# 05_SAMA5D27SOM.net
KiCad netlist of a schematic drawn in Altium Designer
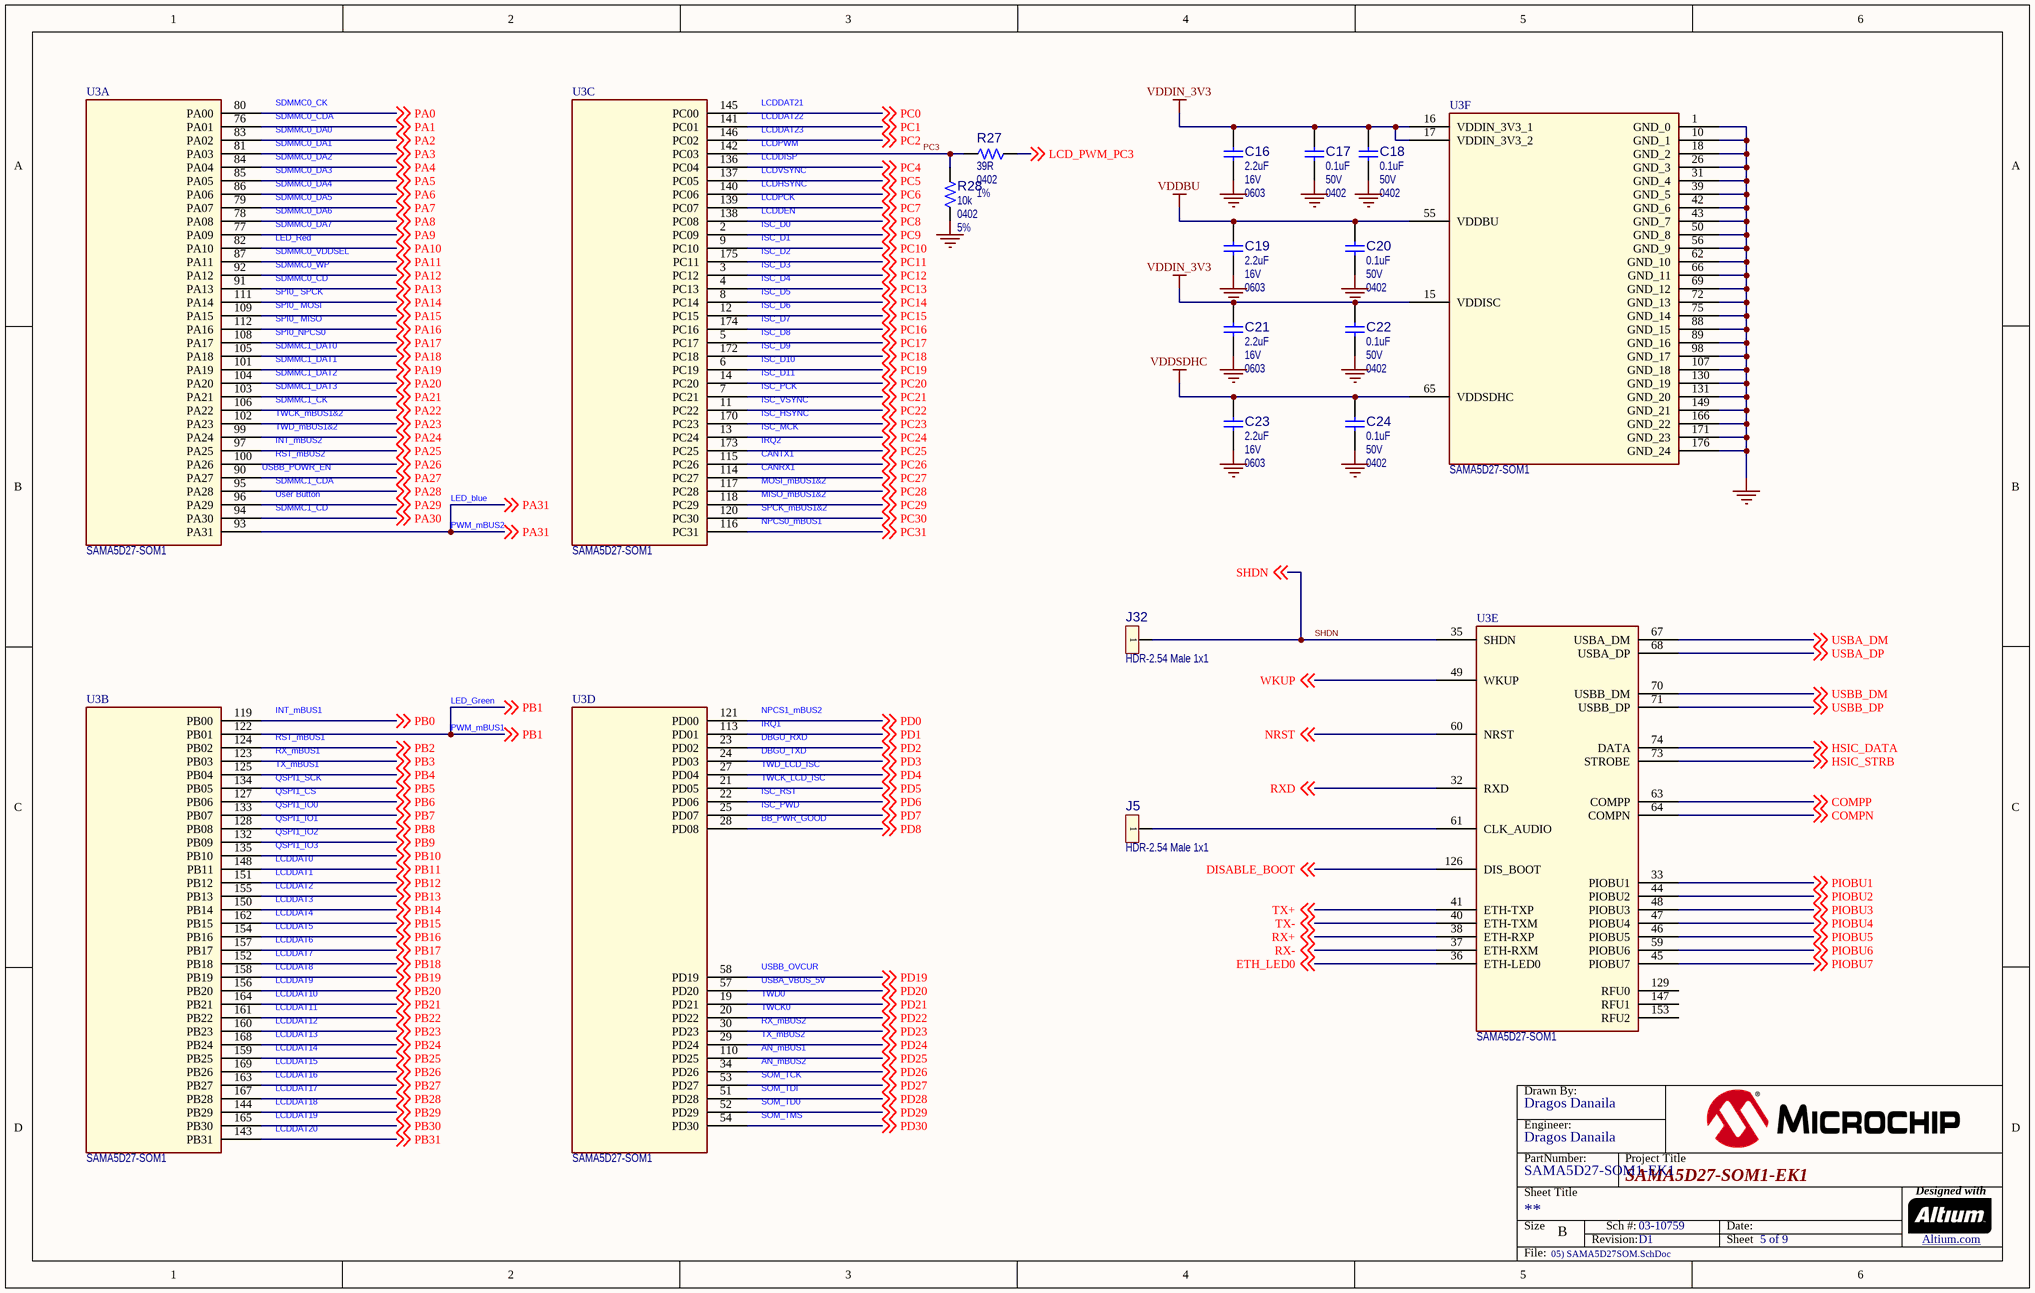
[diagram p0: 05) SAMA5D27SOM.SchDoc]

(export (version "E")
  (design (tool "Eeschema 10.0.6"))
  (components
    (comp (ref "C16")
      (value "2.2uF")
      (footprint "CAP_C_0603")
      (description "Capacitor")
      (fields
        (field (name "VOLTAGE") "16V")
        (field (name "PACKAGE") "0603")
        (field (name "TOLERANCE") "10%")
        (field (name "Comment") "Capacitor NP")
      )
      (libsource (lib "MCHP-CDB") (part "Capacitor NP"))
    )
    (comp (ref "C17")
      (value "0.1uF")
      (footprint "CAP_C_0402")
      (description "Capacitor")
      (fields
        (field (name "VOLTAGE") "50V")
        (field (name "PACKAGE") "0402")
        (field (name "TOLERANCE") "10%")
        (field (name "Comment") "Capacitor NP")
        (field (name "OWNER") "Jamus Griego")
      )
      (libsource (lib "MCHP-CDB") (part "Capacitor NP"))
    )
    (comp (ref "C18")
      (value "0.1uF")
      (footprint "CAP_C_0402")
      (description "Capacitor")
      (fields
        (field (name "VOLTAGE") "50V")
        (field (name "PACKAGE") "0402")
        (field (name "TOLERANCE") "10%")
        (field (name "Comment") "Capacitor NP")
        (field (name "OWNER") "Jamus Griego")
      )
      (libsource (lib "MCHP-CDB") (part "Capacitor NP"))
    )
    (comp (ref "C19")
      (value "2.2uF")
      (footprint "CAP_C_0603")
      (description "Capacitor")
      (fields
        (field (name "VOLTAGE") "16V")
        (field (name "PACKAGE") "0603")
        (field (name "TOLERANCE") "10%")
        (field (name "Comment") "Capacitor NP")
      )
      (libsource (lib "MCHP-CDB") (part "Capacitor NP"))
    )
    (comp (ref "C20")
      (value "0.1uF")
      (footprint "CAP_C_0402")
      (description "Capacitor")
      (fields
        (field (name "VOLTAGE") "50V")
        (field (name "PACKAGE") "0402")
        (field (name "TOLERANCE") "10%")
        (field (name "Comment") "Capacitor NP")
        (field (name "OWNER") "Jamus Griego")
      )
      (libsource (lib "MCHP-CDB") (part "Capacitor NP"))
    )
    (comp (ref "C21")
      (value "2.2uF")
      (footprint "CAP_C_0603")
      (description "Capacitor")
      (fields
        (field (name "VOLTAGE") "16V")
        (field (name "PACKAGE") "0603")
        (field (name "TOLERANCE") "10%")
        (field (name "Comment") "Capacitor NP")
      )
      (libsource (lib "MCHP-CDB") (part "Capacitor NP"))
    )
    (comp (ref "C22")
      (value "0.1uF")
      (footprint "CAP_C_0402")
      (description "Capacitor")
      (fields
        (field (name "VOLTAGE") "50V")
        (field (name "PACKAGE") "0402")
        (field (name "TOLERANCE") "10%")
        (field (name "Comment") "Capacitor NP")
        (field (name "OWNER") "Jamus Griego")
      )
      (libsource (lib "MCHP-CDB") (part "Capacitor NP"))
    )
    (comp (ref "C23")
      (value "2.2uF")
      (footprint "CAP_C_0603")
      (description "Capacitor")
      (fields
        (field (name "VOLTAGE") "16V")
        (field (name "PACKAGE") "0603")
        (field (name "TOLERANCE") "10%")
        (field (name "Comment") "Capacitor NP")
      )
      (libsource (lib "MCHP-CDB") (part "Capacitor NP"))
    )
    (comp (ref "C24")
      (value "0.1uF")
      (footprint "CAP_C_0402")
      (description "Capacitor")
      (fields
        (field (name "VOLTAGE") "50V")
        (field (name "PACKAGE") "0402")
        (field (name "TOLERANCE") "10%")
        (field (name "Comment") "Capacitor NP")
        (field (name "OWNER") "Jamus Griego")
      )
      (libsource (lib "MCHP-CDB") (part "Capacitor NP"))
    )
    (comp (ref "J5")
      (value "HDR-2.54 Male 1x1")
      (footprint "HDR_M_2.54_1x1")
      (description "CON HDR-2.54 Male 1x1 Gold 5.97MH TH VERT")
      (fields (field (name "Comment") "Header 1x1"))
      (libsource (lib "MCHP-CDB") (part "Header 1x1"))
    )
    (comp (ref "J32")
      (value "HDR-2.54 Male 1x1")
      (footprint "HDR_M_2.54_1x1")
      (description "CON HDR-2.54 Male 1x1 Gold 5.97MH TH VERT")
      (fields (field (name "Comment") "Header 1x1"))
      (libsource (lib "MCHP-CDB") (part "Header 1x1"))
    )
    (comp (ref "R27")
      (value "39R")
      (footprint "RES_C_0402")
      (description "Resistor")
      (fields
        (field (name "PACKAGE") "0402")
        (field (name "TOLERANCE") "1%")
        (field (name "POWER") "1/16W")
        (field (name "OWNER") "Sompoch Loboonlert")
      )
      (libsource (lib "MCHP-CDB") (part "Resistor"))
    )
    (comp (ref "R28")
      (value "10k")
      (footprint "RES_C_0402")
      (description "Resistor")
      (fields
        (field (name "PACKAGE") "0402")
        (field (name "TOLERANCE") "5%")
        (field (name "VOLTAGE") "50V")
        (field (name "POWER") "1/16W")
      )
      (libsource (lib "MCHP-CDB") (part "Resistor"))
    )
    (comp (ref "U3")
      (value "SAMA5D27-SOM1")
      (footprint "MOD SOM SAMA5D27-SOM1 40MMX38MM")
      (description "MCHP MCU 32-BIT SOM 500MHz 128kB ETHERNET EEPROM ATSAMA5D27-SOM1 MODULE")
      (fields (field (name "Comment") "MIC7283") (field (name "OWNER") "Dragos Danaila"))
      (libsource (lib "MCHP-CDB") (part "MOD SOM SAMA5D27-DXG-SOM1 40x38mm"))
    )
  )
  (nets
    (net (code "1") (name "/PC3") (class "Default")
      (node (ref "R27") (pin "1") (pinfunction "1_1") (pintype "passive"))
      (node (ref "R28") (pin "1") (pinfunction "1_1") (pintype "passive"))
      (node (ref "U3") (pin "142") (pinfunction "PC03_142") (pintype "passive"))
    )
    (net (code "2") (name "COMPN") (class "Default")
      (node (ref "U3") (pin "64") (pinfunction "COMPN_64") (pintype "passive"))
    )
    (net (code "3") (name "COMPP") (class "Default")
      (node (ref "U3") (pin "63") (pinfunction "COMPP_63") (pintype "passive"))
    )
    (net (code "4") (name "DISABLE_BOOT") (class "Default")
      (node (ref "U3") (pin "126") (pinfunction "DIS_BOOT_126") (pintype "passive"))
    )
    (net (code "5") (name "ETH_LED0") (class "Default")
      (node (ref "U3") (pin "36") (pinfunction "ETH-LED0_36") (pintype "passive"))
    )
    (net (code "6") (name "GND_POWER") (class "Default")
      (node (ref "C16") (pin "2") (pinfunction "2_2") (pintype "passive"))
      (node (ref "C17") (pin "2") (pinfunction "2_2") (pintype "passive"))
      (node (ref "C18") (pin "2") (pinfunction "2_2") (pintype "passive"))
      (node (ref "C19") (pin "2") (pinfunction "2_2") (pintype "passive"))
      (node (ref "C20") (pin "2") (pinfunction "2_2") (pintype "passive"))
      (node (ref "C21") (pin "2") (pinfunction "2_2") (pintype "passive"))
      (node (ref "C22") (pin "2") (pinfunction "2_2") (pintype "passive"))
      (node (ref "C23") (pin "2") (pinfunction "2_2") (pintype "passive"))
      (node (ref "C24") (pin "2") (pinfunction "2_2") (pintype "passive"))
      (node (ref "R28") (pin "2") (pinfunction "2_2") (pintype "passive"))
      (node (ref "U3") (pin "1") (pinfunction "GND_0_1") (pintype "power_in"))
      (node (ref "U3") (pin "10") (pinfunction "GND_1_10") (pintype "power_in"))
      (node (ref "U3") (pin "107") (pinfunction "GND_18_107") (pintype "power_in"))
      (node (ref "U3") (pin "130") (pinfunction "GND_19_130") (pintype "power_in"))
      (node (ref "U3") (pin "131") (pinfunction "GND_20_131") (pintype "power_in"))
      (node (ref "U3") (pin "149") (pinfunction "GND_21_149") (pintype "power_in"))
      (node (ref "U3") (pin "166") (pinfunction "GND_22_166") (pintype "power_in"))
      (node (ref "U3") (pin "171") (pinfunction "GND_23_171") (pintype "power_in"))
      (node (ref "U3") (pin "176") (pinfunction "GND_24_176") (pintype "power_in"))
      (node (ref "U3") (pin "18") (pinfunction "GND_2_18") (pintype "power_in"))
      (node (ref "U3") (pin "26") (pinfunction "GND_3_26") (pintype "power_in"))
      (node (ref "U3") (pin "31") (pinfunction "GND_4_31") (pintype "power_in"))
      (node (ref "U3") (pin "39") (pinfunction "GND_5_39") (pintype "power_in"))
      (node (ref "U3") (pin "42") (pinfunction "GND_6_42") (pintype "power_in"))
      (node (ref "U3") (pin "43") (pinfunction "GND_7_43") (pintype "power_in"))
      (node (ref "U3") (pin "50") (pinfunction "GND_8_50") (pintype "power_in"))
      (node (ref "U3") (pin "56") (pinfunction "GND_9_56") (pintype "power_in"))
      (node (ref "U3") (pin "62") (pinfunction "GND_10_62") (pintype "power_in"))
      (node (ref "U3") (pin "66") (pinfunction "GND_11_66") (pintype "power_in"))
      (node (ref "U3") (pin "69") (pinfunction "GND_12_69") (pintype "power_in"))
      (node (ref "U3") (pin "72") (pinfunction "GND_13_72") (pintype "power_in"))
      (node (ref "U3") (pin "75") (pinfunction "GND_14_75") (pintype "power_in"))
      (node (ref "U3") (pin "88") (pinfunction "GND_15_88") (pintype "power_in"))
      (node (ref "U3") (pin "89") (pinfunction "GND_16_89") (pintype "power_in"))
      (node (ref "U3") (pin "98") (pinfunction "GND_17_98") (pintype "power_in"))
    )
    (net (code "7") (name "HSIC_DATA") (class "Default")
      (node (ref "U3") (pin "74") (pinfunction "DATA_74") (pintype "passive"))
    )
    (net (code "8") (name "HSIC_STRB") (class "Default")
      (node (ref "U3") (pin "73") (pinfunction "STROBE_73") (pintype "passive"))
    )
    (net (code "9") (name "LCD_PWM_PC3") (class "Default")
      (node (ref "R27") (pin "2") (pinfunction "2_2") (pintype "passive"))
    )
    (net (code "10") (name "NRST") (class "Default")
      (node (ref "U3") (pin "60") (pinfunction "NRST_60") (pintype "passive"))
    )
    (net (code "11") (name "Net-(U3E-CLK_AUDIO)") (class "Default")
      (node (ref "J5") (pin "1") (pinfunction "1_1") (pintype "passive"))
      (node (ref "U3") (pin "61") (pinfunction "CLK_AUDIO_61") (pintype "passive"))
    )
    (net (code "12") (name "PA0") (class "Default")
      (node (ref "U3") (pin "80") (pinfunction "PA00_80") (pintype "passive"))
    )
    (net (code "13") (name "PA1") (class "Default")
      (node (ref "U3") (pin "76") (pinfunction "PA01_76") (pintype "passive"))
    )
    (net (code "14") (name "PA2") (class "Default")
      (node (ref "U3") (pin "83") (pinfunction "PA02_83") (pintype "passive"))
    )
    (net (code "15") (name "PA3") (class "Default")
      (node (ref "U3") (pin "81") (pinfunction "PA03_81") (pintype "passive"))
    )
    (net (code "16") (name "PA4") (class "Default")
      (node (ref "U3") (pin "84") (pinfunction "PA04_84") (pintype "passive"))
    )
    (net (code "17") (name "PA5") (class "Default")
      (node (ref "U3") (pin "85") (pinfunction "PA05_85") (pintype "passive"))
    )
    (net (code "18") (name "PA6") (class "Default")
      (node (ref "U3") (pin "86") (pinfunction "PA06_86") (pintype "passive"))
    )
    (net (code "19") (name "PA7") (class "Default")
      (node (ref "U3") (pin "79") (pinfunction "PA07_79") (pintype "passive"))
    )
    (net (code "20") (name "PA8") (class "Default")
      (node (ref "U3") (pin "78") (pinfunction "PA08_78") (pintype "passive"))
    )
    (net (code "21") (name "PA9") (class "Default")
      (node (ref "U3") (pin "77") (pinfunction "PA09_77") (pintype "passive"))
    )
    (net (code "22") (name "PA10") (class "Default")
      (node (ref "U3") (pin "82") (pinfunction "PA10_82") (pintype "passive"))
    )
    (net (code "23") (name "PA11") (class "Default")
      (node (ref "U3") (pin "87") (pinfunction "PA11_87") (pintype "passive"))
    )
    (net (code "24") (name "PA12") (class "Default")
      (node (ref "U3") (pin "92") (pinfunction "PA12_92") (pintype "passive"))
    )
    (net (code "25") (name "PA13") (class "Default")
      (node (ref "U3") (pin "91") (pinfunction "PA13_91") (pintype "passive"))
    )
    (net (code "26") (name "PA14") (class "Default")
      (node (ref "U3") (pin "111") (pinfunction "PA14_111") (pintype "passive"))
    )
    (net (code "27") (name "PA15") (class "Default")
      (node (ref "U3") (pin "109") (pinfunction "PA15_109") (pintype "passive"))
    )
    (net (code "28") (name "PA16") (class "Default")
      (node (ref "U3") (pin "112") (pinfunction "PA16_112") (pintype "passive"))
    )
    (net (code "29") (name "PA17") (class "Default")
      (node (ref "U3") (pin "108") (pinfunction "PA17_108") (pintype "passive"))
    )
    (net (code "30") (name "PA18") (class "Default")
      (node (ref "U3") (pin "105") (pinfunction "PA18_105") (pintype "passive"))
    )
    (net (code "31") (name "PA19") (class "Default")
      (node (ref "U3") (pin "101") (pinfunction "PA19_101") (pintype "passive"))
    )
    (net (code "32") (name "PA20") (class "Default")
      (node (ref "U3") (pin "104") (pinfunction "PA20_104") (pintype "passive"))
    )
    (net (code "33") (name "PA21") (class "Default")
      (node (ref "U3") (pin "103") (pinfunction "PA21_103") (pintype "passive"))
    )
    (net (code "34") (name "PA22") (class "Default")
      (node (ref "U3") (pin "106") (pinfunction "PA22_106") (pintype "passive"))
    )
    (net (code "35") (name "PA23") (class "Default")
      (node (ref "U3") (pin "102") (pinfunction "PA23_102") (pintype "passive"))
    )
    (net (code "36") (name "PA24") (class "Default")
      (node (ref "U3") (pin "99") (pinfunction "PA24_99") (pintype "passive"))
    )
    (net (code "37") (name "PA25") (class "Default")
      (node (ref "U3") (pin "97") (pinfunction "PA25_97") (pintype "passive"))
    )
    (net (code "38") (name "PA26") (class "Default")
      (node (ref "U3") (pin "100") (pinfunction "PA26_100") (pintype "passive"))
    )
    (net (code "39") (name "PA27") (class "Default")
      (node (ref "U3") (pin "90") (pinfunction "PA27_90") (pintype "passive"))
    )
    (net (code "40") (name "PA28") (class "Default")
      (node (ref "U3") (pin "95") (pinfunction "PA28_95") (pintype "passive"))
    )
    (net (code "41") (name "PA29") (class "Default")
      (node (ref "U3") (pin "96") (pinfunction "PA29_96") (pintype "passive"))
    )
    (net (code "42") (name "PA30") (class "Default")
      (node (ref "U3") (pin "94") (pinfunction "PA30_94") (pintype "passive"))
    )
    (net (code "43") (name "PA31") (class "Default")
      (node (ref "U3") (pin "93") (pinfunction "PA31_93") (pintype "passive"))
    )
    (net (code "44") (name "PB0") (class "Default")
      (node (ref "U3") (pin "119") (pinfunction "PB00_119") (pintype "passive"))
    )
    (net (code "45") (name "PB1") (class "Default")
      (node (ref "U3") (pin "122") (pinfunction "PB01_122") (pintype "passive"))
    )
    (net (code "46") (name "PB2") (class "Default")
      (node (ref "U3") (pin "124") (pinfunction "PB02_124") (pintype "passive"))
    )
    (net (code "47") (name "PB3") (class "Default")
      (node (ref "U3") (pin "123") (pinfunction "PB03_123") (pintype "passive"))
    )
    (net (code "48") (name "PB4") (class "Default")
      (node (ref "U3") (pin "125") (pinfunction "PB04_125") (pintype "passive"))
    )
    (net (code "49") (name "PB5") (class "Default")
      (node (ref "U3") (pin "134") (pinfunction "PB05_134") (pintype "passive"))
    )
    (net (code "50") (name "PB6") (class "Default")
      (node (ref "U3") (pin "127") (pinfunction "PB06_127") (pintype "passive"))
    )
    (net (code "51") (name "PB7") (class "Default")
      (node (ref "U3") (pin "133") (pinfunction "PB07_133") (pintype "passive"))
    )
    (net (code "52") (name "PB8") (class "Default")
      (node (ref "U3") (pin "128") (pinfunction "PB08_128") (pintype "passive"))
    )
    (net (code "53") (name "PB9") (class "Default")
      (node (ref "U3") (pin "132") (pinfunction "PB09_132") (pintype "passive"))
    )
    (net (code "54") (name "PB10") (class "Default")
      (node (ref "U3") (pin "135") (pinfunction "PB10_135") (pintype "passive"))
    )
    (net (code "55") (name "PB11") (class "Default")
      (node (ref "U3") (pin "148") (pinfunction "PB11_148") (pintype "passive"))
    )
    (net (code "56") (name "PB12") (class "Default")
      (node (ref "U3") (pin "151") (pinfunction "PB12_151") (pintype "passive"))
    )
    (net (code "57") (name "PB13") (class "Default")
      (node (ref "U3") (pin "155") (pinfunction "PB13_155") (pintype "passive"))
    )
    (net (code "58") (name "PB14") (class "Default")
      (node (ref "U3") (pin "150") (pinfunction "PB14_150") (pintype "passive"))
    )
    (net (code "59") (name "PB15") (class "Default")
      (node (ref "U3") (pin "162") (pinfunction "PB15_162") (pintype "passive"))
    )
    (net (code "60") (name "PB16") (class "Default")
      (node (ref "U3") (pin "154") (pinfunction "PB16_154") (pintype "passive"))
    )
    (net (code "61") (name "PB17") (class "Default")
      (node (ref "U3") (pin "157") (pinfunction "PB17_157") (pintype "passive"))
    )
    (net (code "62") (name "PB18") (class "Default")
      (node (ref "U3") (pin "152") (pinfunction "PB18_152") (pintype "passive"))
    )
    (net (code "63") (name "PB19") (class "Default")
      (node (ref "U3") (pin "158") (pinfunction "PB19_158") (pintype "passive"))
    )
    (net (code "64") (name "PB20") (class "Default")
      (node (ref "U3") (pin "156") (pinfunction "PB20_156") (pintype "passive"))
    )
    (net (code "65") (name "PB21") (class "Default")
      (node (ref "U3") (pin "164") (pinfunction "PB21_164") (pintype "passive"))
    )
    (net (code "66") (name "PB22") (class "Default")
      (node (ref "U3") (pin "161") (pinfunction "PB22_161") (pintype "passive"))
    )
    (net (code "67") (name "PB23") (class "Default")
      (node (ref "U3") (pin "160") (pinfunction "PB23_160") (pintype "passive"))
    )
    (net (code "68") (name "PB24") (class "Default")
      (node (ref "U3") (pin "168") (pinfunction "PB24_168") (pintype "passive"))
    )
    (net (code "69") (name "PB25") (class "Default")
      (node (ref "U3") (pin "159") (pinfunction "PB25_159") (pintype "passive"))
    )
    (net (code "70") (name "PB26") (class "Default")
      (node (ref "U3") (pin "169") (pinfunction "PB26_169") (pintype "passive"))
    )
    (net (code "71") (name "PB27") (class "Default")
      (node (ref "U3") (pin "163") (pinfunction "PB27_163") (pintype "passive"))
    )
    (net (code "72") (name "PB28") (class "Default")
      (node (ref "U3") (pin "167") (pinfunction "PB28_167") (pintype "passive"))
    )
    (net (code "73") (name "PB29") (class "Default")
      (node (ref "U3") (pin "144") (pinfunction "PB29_144") (pintype "passive"))
    )
    (net (code "74") (name "PB30") (class "Default")
      (node (ref "U3") (pin "165") (pinfunction "PB30_165") (pintype "passive"))
    )
    (net (code "75") (name "PB31") (class "Default")
      (node (ref "U3") (pin "143") (pinfunction "PB31_143") (pintype "passive"))
    )
    (net (code "76") (name "PC0") (class "Default")
      (node (ref "U3") (pin "145") (pinfunction "PC00_145") (pintype "passive"))
    )
    (net (code "77") (name "PC1") (class "Default")
      (node (ref "U3") (pin "141") (pinfunction "PC01_141") (pintype "passive"))
    )
    (net (code "78") (name "PC2") (class "Default")
      (node (ref "U3") (pin "146") (pinfunction "PC02_146") (pintype "passive"))
    )
    (net (code "79") (name "PC4") (class "Default")
      (node (ref "U3") (pin "136") (pinfunction "PC04_136") (pintype "passive"))
    )
    (net (code "80") (name "PC5") (class "Default")
      (node (ref "U3") (pin "137") (pinfunction "PC05_137") (pintype "passive"))
    )
    (net (code "81") (name "PC6") (class "Default")
      (node (ref "U3") (pin "140") (pinfunction "PC06_140") (pintype "passive"))
    )
    (net (code "82") (name "PC7") (class "Default")
      (node (ref "U3") (pin "139") (pinfunction "PC07_139") (pintype "passive"))
    )
    (net (code "83") (name "PC8") (class "Default")
      (node (ref "U3") (pin "138") (pinfunction "PC08_138") (pintype "passive"))
    )
    (net (code "84") (name "PC9") (class "Default")
      (node (ref "U3") (pin "2") (pinfunction "PC09_2") (pintype "passive"))
    )
    (net (code "85") (name "PC10") (class "Default")
      (node (ref "U3") (pin "9") (pinfunction "PC10_9") (pintype "passive"))
    )
    (net (code "86") (name "PC11") (class "Default")
      (node (ref "U3") (pin "175") (pinfunction "PC11_175") (pintype "passive"))
    )
    (net (code "87") (name "PC12") (class "Default")
      (node (ref "U3") (pin "3") (pinfunction "PC12_3") (pintype "passive"))
    )
    (net (code "88") (name "PC13") (class "Default")
      (node (ref "U3") (pin "4") (pinfunction "PC13_4") (pintype "passive"))
    )
    (net (code "89") (name "PC14") (class "Default")
      (node (ref "U3") (pin "8") (pinfunction "PC14_8") (pintype "passive"))
    )
    (net (code "90") (name "PC15") (class "Default")
      (node (ref "U3") (pin "12") (pinfunction "PC15_12") (pintype "passive"))
    )
    (net (code "91") (name "PC16") (class "Default")
      (node (ref "U3") (pin "174") (pinfunction "PC16_174") (pintype "passive"))
    )
    (net (code "92") (name "PC17") (class "Default")
      (node (ref "U3") (pin "5") (pinfunction "PC17_5") (pintype "passive"))
    )
    (net (code "93") (name "PC18") (class "Default")
      (node (ref "U3") (pin "172") (pinfunction "PC18_172") (pintype "passive"))
    )
    (net (code "94") (name "PC19") (class "Default")
      (node (ref "U3") (pin "6") (pinfunction "PC19_6") (pintype "passive"))
    )
    (net (code "95") (name "PC20") (class "Default")
      (node (ref "U3") (pin "14") (pinfunction "PC20_14") (pintype "passive"))
    )
    (net (code "96") (name "PC21") (class "Default")
      (node (ref "U3") (pin "7") (pinfunction "PC21_7") (pintype "passive"))
    )
    (net (code "97") (name "PC22") (class "Default")
      (node (ref "U3") (pin "11") (pinfunction "PC22_11") (pintype "passive"))
    )
    (net (code "98") (name "PC23") (class "Default")
      (node (ref "U3") (pin "170") (pinfunction "PC23_170") (pintype "passive"))
    )
    (net (code "99") (name "PC24") (class "Default")
      (node (ref "U3") (pin "13") (pinfunction "PC24_13") (pintype "passive"))
    )
    (net (code "100") (name "PC25") (class "Default")
      (node (ref "U3") (pin "173") (pinfunction "PC25_173") (pintype "passive"))
    )
    (net (code "101") (name "PC26") (class "Default")
      (node (ref "U3") (pin "115") (pinfunction "PC26_115") (pintype "passive"))
    )
    (net (code "102") (name "PC27") (class "Default")
      (node (ref "U3") (pin "114") (pinfunction "PC27_114") (pintype "passive"))
    )
    (net (code "103") (name "PC28") (class "Default")
      (node (ref "U3") (pin "117") (pinfunction "PC28_117") (pintype "passive"))
    )
    (net (code "104") (name "PC29") (class "Default")
      (node (ref "U3") (pin "118") (pinfunction "PC29_118") (pintype "passive"))
    )
    (net (code "105") (name "PC30") (class "Default")
      (node (ref "U3") (pin "120") (pinfunction "PC30_120") (pintype "passive"))
    )
    (net (code "106") (name "PC31") (class "Default")
      (node (ref "U3") (pin "116") (pinfunction "PC31_116") (pintype "passive"))
    )
    (net (code "107") (name "PD0") (class "Default")
      (node (ref "U3") (pin "121") (pinfunction "PD00_121") (pintype "passive"))
    )
    (net (code "108") (name "PD1") (class "Default")
      (node (ref "U3") (pin "113") (pinfunction "PD01_113") (pintype "passive"))
    )
    (net (code "109") (name "PD2") (class "Default")
      (node (ref "U3") (pin "23") (pinfunction "PD02_23") (pintype "passive"))
    )
    (net (code "110") (name "PD3") (class "Default")
      (node (ref "U3") (pin "24") (pinfunction "PD03_24") (pintype "passive"))
    )
    (net (code "111") (name "PD4") (class "Default")
      (node (ref "U3") (pin "27") (pinfunction "PD04_27") (pintype "passive"))
    )
    (net (code "112") (name "PD5") (class "Default")
      (node (ref "U3") (pin "21") (pinfunction "PD05_21") (pintype "passive"))
    )
    (net (code "113") (name "PD6") (class "Default")
      (node (ref "U3") (pin "22") (pinfunction "PD06_22") (pintype "passive"))
    )
    (net (code "114") (name "PD7") (class "Default")
      (node (ref "U3") (pin "25") (pinfunction "PD07_25") (pintype "passive"))
    )
    (net (code "115") (name "PD8") (class "Default")
      (node (ref "U3") (pin "28") (pinfunction "PD08_28") (pintype "passive"))
    )
    (net (code "116") (name "PD19") (class "Default")
      (node (ref "U3") (pin "58") (pinfunction "PD19_58") (pintype "passive"))
    )
    (net (code "117") (name "PD20") (class "Default")
      (node (ref "U3") (pin "57") (pinfunction "PD20_57") (pintype "passive"))
    )
    (net (code "118") (name "PD21") (class "Default")
      (node (ref "U3") (pin "19") (pinfunction "PD21_19") (pintype "passive"))
    )
    (net (code "119") (name "PD22") (class "Default")
      (node (ref "U3") (pin "20") (pinfunction "PD22_20") (pintype "passive"))
    )
    (net (code "120") (name "PD23") (class "Default")
      (node (ref "U3") (pin "30") (pinfunction "PD23_30") (pintype "passive"))
    )
    (net (code "121") (name "PD24") (class "Default")
      (node (ref "U3") (pin "29") (pinfunction "PD24_29") (pintype "passive"))
    )
    (net (code "122") (name "PD25") (class "Default")
      (node (ref "U3") (pin "110") (pinfunction "PD25_110") (pintype "passive"))
    )
    (net (code "123") (name "PD26") (class "Default")
      (node (ref "U3") (pin "34") (pinfunction "PD26_34") (pintype "passive"))
    )
    (net (code "124") (name "PD27") (class "Default")
      (node (ref "U3") (pin "53") (pinfunction "PD27_53") (pintype "passive"))
    )
    (net (code "125") (name "PD28") (class "Default")
      (node (ref "U3") (pin "51") (pinfunction "PD28_51") (pintype "passive"))
    )
    (net (code "126") (name "PD29") (class "Default")
      (node (ref "U3") (pin "52") (pinfunction "PD29_52") (pintype "passive"))
    )
    (net (code "127") (name "PD30") (class "Default")
      (node (ref "U3") (pin "54") (pinfunction "PD30_54") (pintype "passive"))
    )
    (net (code "128") (name "PIOBU1") (class "Default")
      (node (ref "U3") (pin "33") (pinfunction "PIOBU1_33") (pintype "passive"))
    )
    (net (code "129") (name "PIOBU2") (class "Default")
      (node (ref "U3") (pin "44") (pinfunction "PIOBU2_44") (pintype "passive"))
    )
    (net (code "130") (name "PIOBU3") (class "Default")
      (node (ref "U3") (pin "48") (pinfunction "PIOBU3_48") (pintype "passive"))
    )
    (net (code "131") (name "PIOBU4") (class "Default")
      (node (ref "U3") (pin "47") (pinfunction "PIOBU4_47") (pintype "passive"))
    )
    (net (code "132") (name "PIOBU5") (class "Default")
      (node (ref "U3") (pin "46") (pinfunction "PIOBU5_46") (pintype "passive"))
    )
    (net (code "133") (name "PIOBU6") (class "Default")
      (node (ref "U3") (pin "59") (pinfunction "PIOBU6_59") (pintype "passive"))
    )
    (net (code "134") (name "PIOBU7") (class "Default")
      (node (ref "U3") (pin "45") (pinfunction "PIOBU7_45") (pintype "passive"))
    )
    (net (code "135") (name "RX+") (class "Default")
      (node (ref "U3") (pin "38") (pinfunction "ETH-RXP_38") (pintype "passive"))
    )
    (net (code "136") (name "RX-") (class "Default")
      (node (ref "U3") (pin "37") (pinfunction "ETH-RXM_37") (pintype "passive"))
    )
    (net (code "137") (name "RXD") (class "Default")
      (node (ref "U3") (pin "32") (pinfunction "RXD_32") (pintype "passive"))
    )
    (net (code "138") (name "SHDN") (class "Default")
      (node (ref "J32") (pin "1") (pinfunction "1_1") (pintype "passive"))
      (node (ref "U3") (pin "35") (pinfunction "SHDN_35") (pintype "passive"))
    )
    (net (code "139") (name "TX+") (class "Default")
      (node (ref "U3") (pin "41") (pinfunction "ETH-TXP_41") (pintype "passive"))
    )
    (net (code "140") (name "TX-") (class "Default")
      (node (ref "U3") (pin "40") (pinfunction "ETH-TXM_40") (pintype "passive"))
    )
    (net (code "141") (name "USBA_DM") (class "Default")
      (node (ref "U3") (pin "67") (pinfunction "USBA_DM_67") (pintype "passive"))
    )
    (net (code "142") (name "USBA_DP") (class "Default")
      (node (ref "U3") (pin "68") (pinfunction "USBA_DP_68") (pintype "passive"))
    )
    (net (code "143") (name "USBB_DM") (class "Default")
      (node (ref "U3") (pin "70") (pinfunction "USBB_DM_70") (pintype "passive"))
    )
    (net (code "144") (name "USBB_DP") (class "Default")
      (node (ref "U3") (pin "71") (pinfunction "USBB_DP_71") (pintype "passive"))
    )
    (net (code "145") (name "VDDBU") (class "Default")
      (node (ref "C19") (pin "1") (pinfunction "1_1") (pintype "passive"))
      (node (ref "C20") (pin "1") (pinfunction "1_1") (pintype "passive"))
      (node (ref "U3") (pin "55") (pinfunction "VDDBU_55") (pintype "passive"))
    )
    (net (code "146") (name "VDDIN_3V3") (class "Default")
      (node (ref "C16") (pin "1") (pinfunction "1_1") (pintype "passive"))
      (node (ref "C17") (pin "1") (pinfunction "1_1") (pintype "passive"))
      (node (ref "C18") (pin "1") (pinfunction "1_1") (pintype "passive"))
      (node (ref "C21") (pin "1") (pinfunction "1_1") (pintype "passive"))
      (node (ref "C22") (pin "1") (pinfunction "1_1") (pintype "passive"))
      (node (ref "U3") (pin "15") (pinfunction "VDDISC_15") (pintype "passive"))
      (node (ref "U3") (pin "16") (pinfunction "VDDIN_3V3_1_16") (pintype "passive"))
      (node (ref "U3") (pin "17") (pinfunction "VDDIN_3V3_2_17") (pintype "passive"))
    )
    (net (code "147") (name "VDDSDHC") (class "Default")
      (node (ref "C23") (pin "1") (pinfunction "1_1") (pintype "passive"))
      (node (ref "C24") (pin "1") (pinfunction "1_1") (pintype "passive"))
      (node (ref "U3") (pin "65") (pinfunction "VDDSDHC_65") (pintype "passive"))
    )
    (net (code "148") (name "WKUP") (class "Default")
      (node (ref "U3") (pin "49") (pinfunction "WKUP_49") (pintype "passive"))
    )
    (net (code "149") (name "unconnected-(U3E-RFU0-Pad129)") (class "Default")
      (node (ref "U3") (pin "129") (pinfunction "RFU0_129") (pintype "passive"))
    )
    (net (code "150") (name "unconnected-(U3E-RFU1-Pad147)") (class "Default")
      (node (ref "U3") (pin "147") (pinfunction "RFU1_147") (pintype "passive"))
    )
    (net (code "151") (name "unconnected-(U3E-RFU2-Pad153)") (class "Default")
      (node (ref "U3") (pin "153") (pinfunction "RFU2_153") (pintype "passive"))
    )
  )
)
